# MEM_M_V1.net
KiCad netlist of a schematic drawn in Altium Designer
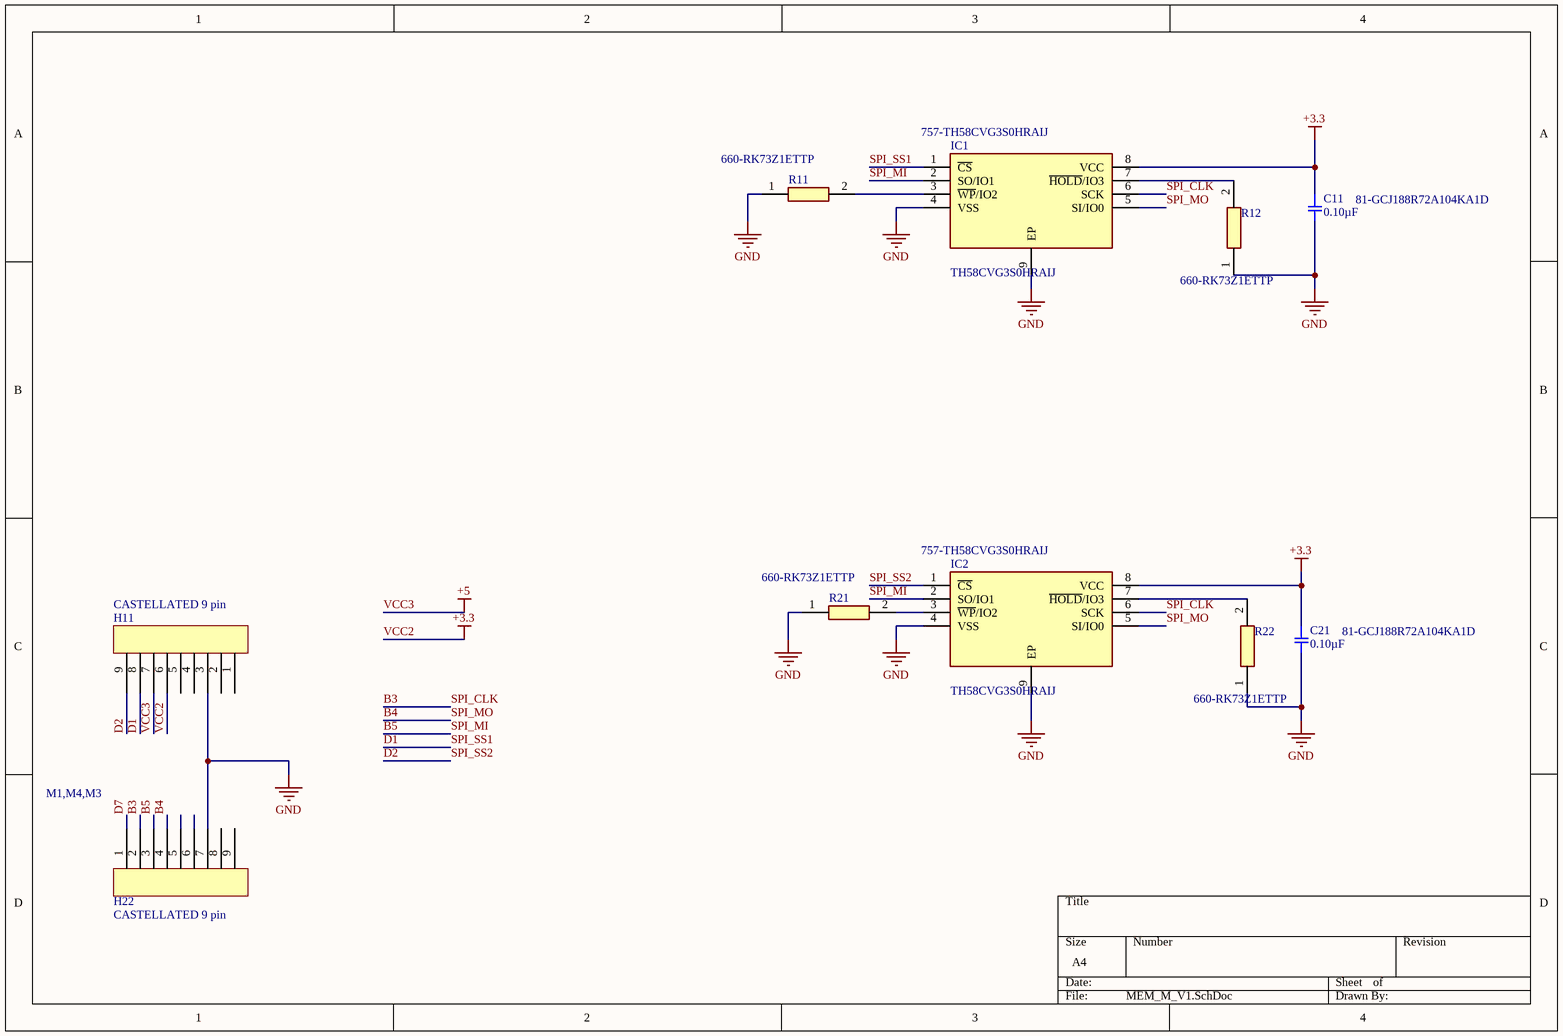
[diagram p0: MEM_M_V1.SchDoc]

(export (version "E")
  (design (tool "Eeschema 10.0.6"))
  (components
    (comp (ref "C11")
      (value "0.10µF")
      (footprint "SMD-0603C")
      (description "CAP CER 0.1UF 100V X7R 0603")
      (fields
        (field (name "PART NUMBER") "GCJ188R72A104KA01D")
        (field (name "DIGI-KEY PART NUMBER") "490-13420-1-ND")
        (field (name "SUPPLIER PART NUMBER 1") "81-GCJ188R72A104KA1D")
      )
      (libsource (lib "cap_murata") (part "CAPACITOR"))
    )
    (comp (ref "C21")
      (value "0.10µF")
      (footprint "SMD-0603C")
      (description "CAP CER 0.1UF 100V X7R 0603")
      (fields
        (field (name "PART NUMBER") "GCJ188R72A104KA01D")
        (field (name "DIGI-KEY PART NUMBER") "490-13420-1-ND")
        (field (name "SUPPLIER PART NUMBER 1") "81-GCJ188R72A104KA1D")
      )
      (libsource (lib "cap_murata") (part "CAPACITOR"))
    )
    (comp (ref "H11")
      (value "CASTELLATED 9 pin")
      (footprint "CASTELLATED 9 pin")
      (libsource (lib "USIB") (part "CASTELLATED 9 pin"))
    )
    (comp (ref "H22")
      (value "CASTELLATED 9 pin")
      (footprint "CASTELLATED 9 pin")
      (libsource (lib "") (part "CASTELLATED 9 pin_1"))
    )
    (comp (ref "IC1")
      (value "TH58CVG3S0HRAIJ")
      (footprint "SamacSys:SON127P800X600X80-9N-D")
      (description "Integrated Circuit")
      (fields (field (name "SUPPLIER PART NUMBER 1") "757-TH58CVG3S0HRAIJ"))
      (libsource (lib "*") (part "TH58CVG3S0HRAIJ"))
    )
    (comp (ref "IC2")
      (value "TH58CVG3S0HRAIJ")
      (footprint "SamacSys:SON127P800X600X80-9N-D")
      (description "Integrated Circuit")
      (fields (field (name "SUPPLIER PART NUMBER 1") "757-TH58CVG3S0HRAIJ"))
      (libsource (lib "*") (part "TH58CVG3S0HRAIJ"))
    )
    (comp (ref "R11")
      (value "RK73Z1ETTP")
      (footprint "SamacSys:RESC1005X40N")
      (description "Resistor")
      (fields (field (name "SUPPLIER PART NUMBER 1") "660-RK73Z1ETTP"))
      (libsource (lib "") (part "RK73Z1ETTP_1"))
    )
    (comp (ref "R12")
      (value "RK73Z1ETTP")
      (footprint "SamacSys:RESC1005X40N")
      (description "Resistor")
      (fields (field (name "SUPPLIER PART NUMBER 1") "660-RK73Z1ETTP"))
      (libsource (lib "SamacSys") (part "RK73Z1ETTP"))
    )
    (comp (ref "R21")
      (value "RK73Z1ETTP")
      (footprint "SamacSys:RESC1005X40N")
      (description "Resistor")
      (fields (field (name "SUPPLIER PART NUMBER 1") "660-RK73Z1ETTP"))
      (libsource (lib "") (part "RK73Z1ETTP_1"))
    )
    (comp (ref "R22")
      (value "RK73Z1ETTP")
      (footprint "SamacSys:RESC1005X40N")
      (description "Resistor")
      (fields (field (name "SUPPLIER PART NUMBER 1") "660-RK73Z1ETTP"))
      (libsource (lib "SamacSys") (part "RK73Z1ETTP"))
    )
  )
  (nets
    (net (code "1") (name "+3.3") (class "Default")
      (node (ref "C11") (pin "1") (pinfunction "1_1") (pintype "passive"))
      (node (ref "C21") (pin "1") (pinfunction "1_1") (pintype "passive"))
      (node (ref "H11") (pin "6") (pintype "passive"))
      (node (ref "IC1") (pin "8") (pinfunction "VCC_8") (pintype "passive"))
      (node (ref "IC2") (pin "8") (pinfunction "VCC_8") (pintype "passive"))
    )
    (net (code "2") (name "+5") (class "Default") (node (ref "H11") (pin "7") (pintype "passive")))
    (net (code "3") (name "/B3") (class "Default")
      (node (ref "H22") (pin "2") (pintype "passive"))
      (node (ref "IC1") (pin "6") (pinfunction "SCK_6") (pintype "passive"))
      (node (ref "IC2") (pin "6") (pinfunction "SCK_6") (pintype "passive"))
    )
    (net (code "4") (name "/B4") (class "Default")
      (node (ref "H22") (pin "4") (pintype "passive"))
      (node (ref "IC1") (pin "5") (pinfunction "SI/IO0_5") (pintype "passive"))
      (node (ref "IC2") (pin "5") (pinfunction "SI/IO0_5") (pintype "passive"))
    )
    (net (code "5") (name "/B5") (class "Default")
      (node (ref "H22") (pin "3") (pintype "passive"))
      (node (ref "IC1") (pin "2") (pinfunction "SO/IO1_2") (pintype "passive"))
      (node (ref "IC2") (pin "2") (pinfunction "SO/IO1_2") (pintype "passive"))
    )
    (net (code "6") (name "/D1") (class "Default")
      (node (ref "H11") (pin "8") (pintype "passive"))
      (node (ref "IC1") (pin "1") (pinfunction "~{CS}_1") (pintype "passive"))
    )
    (net (code "7") (name "/D2") (class "Default")
      (node (ref "H11") (pin "9") (pintype "passive"))
      (node (ref "IC2") (pin "1") (pinfunction "~{CS}_1") (pintype "passive"))
    )
    (net (code "8") (name "/D7") (class "Default") (node (ref "H22") (pin "1") (pintype "passive")))
    (net (code "9") (name "GND") (class "Default")
      (node (ref "C11") (pin "2") (pinfunction "2_2") (pintype "passive"))
      (node (ref "C21") (pin "2") (pinfunction "2_2") (pintype "passive"))
      (node (ref "H11") (pin "3") (pintype "passive"))
      (node (ref "H22") (pin "7") (pintype "passive"))
      (node (ref "IC1") (pin "4") (pinfunction "VSS_4") (pintype "passive"))
      (node (ref "IC1") (pin "9") (pinfunction "EP_9") (pintype "passive"))
      (node (ref "IC2") (pin "4") (pinfunction "VSS_4") (pintype "passive"))
      (node (ref "IC2") (pin "9") (pinfunction "EP_9") (pintype "passive"))
      (node (ref "R11") (pin "1") (pinfunction "1_1") (pintype "passive"))
      (node (ref "R12") (pin "1") (pinfunction "1_1") (pintype "passive"))
      (node (ref "R21") (pin "1") (pinfunction "1_1") (pintype "passive"))
      (node (ref "R22") (pin "1") (pinfunction "1_1") (pintype "passive"))
    )
    (net (code "10") (name "Net-(IC1-~{HOLD}{slash}IO3)") (class "Default")
      (node (ref "IC1") (pin "7") (pinfunction "~{HOLD}/IO3_7") (pintype "passive"))
      (node (ref "R12") (pin "2") (pinfunction "2_2") (pintype "passive"))
    )
    (net (code "11") (name "Net-(IC1-~{WP}{slash}IO2)") (class "Default")
      (node (ref "IC1") (pin "3") (pinfunction "~{WP}/IO2_3") (pintype "passive"))
      (node (ref "R11") (pin "2") (pinfunction "2_2") (pintype "passive"))
    )
    (net (code "12") (name "Net-(IC2-~{HOLD}{slash}IO3)") (class "Default")
      (node (ref "IC2") (pin "7") (pinfunction "~{HOLD}/IO3_7") (pintype "passive"))
      (node (ref "R22") (pin "2") (pinfunction "2_2") (pintype "passive"))
    )
    (net (code "13") (name "Net-(IC2-~{WP}{slash}IO2)") (class "Default")
      (node (ref "IC2") (pin "3") (pinfunction "~{WP}/IO2_3") (pintype "passive"))
      (node (ref "R21") (pin "2") (pinfunction "2_2") (pintype "passive"))
    )
    (net (code "14") (name "unconnected-(H11-Pad1)") (class "Default")
      (node (ref "H11") (pin "1") (pintype "passive"))
    )
    (net (code "15") (name "unconnected-(H11-Pad2)") (class "Default")
      (node (ref "H11") (pin "2") (pintype "passive"))
    )
    (net (code "16") (name "unconnected-(H11-Pad4)") (class "Default")
      (node (ref "H11") (pin "4") (pintype "passive"))
    )
    (net (code "17") (name "unconnected-(H11-Pad5)") (class "Default")
      (node (ref "H11") (pin "5") (pintype "passive"))
    )
    (net (code "18") (name "unconnected-(H22-Pad5)") (class "Default")
      (node (ref "H22") (pin "5") (pintype "passive"))
    )
    (net (code "19") (name "unconnected-(H22-Pad6)") (class "Default")
      (node (ref "H22") (pin "6") (pintype "passive"))
    )
    (net (code "20") (name "unconnected-(H22-Pad8)") (class "Default")
      (node (ref "H22") (pin "8") (pintype "passive"))
    )
    (net (code "21") (name "unconnected-(H22-Pad9)") (class "Default")
      (node (ref "H22") (pin "9") (pintype "passive"))
    )
  )
)
